# Motor_3.net
KiCad netlist of a schematic drawn in Altium Designer
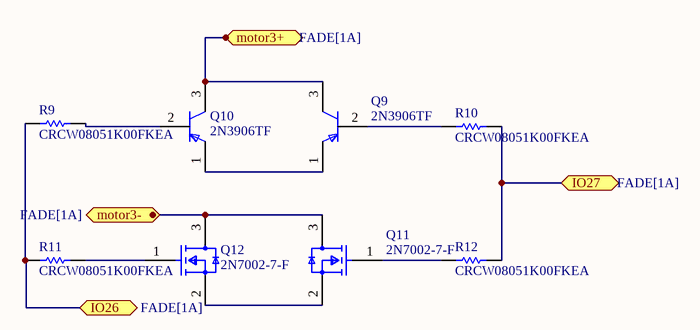
[diagram p0: Motor_3.SchDoc]

(export (version "E")
  (design (tool "Eeschema 10.0.6"))
  (components
    (comp (ref "Q9")
      (value "2N3906TF")
      (footprint "FP-135AR-MFG")
      (description "2N3906TF Small Signal Bipolar Transistor, 0.2A I(C), 40V V(BR)CEO, 1-Element, PNP, Silicon, TO-92")
      (libsource (lib "Altium Content Vault") (part "40d2b7e180a7bcff784209620afba3e"))
    )
    (comp (ref "Q10")
      (value "2N3906TF")
      (footprint "FP-135AR-MFG")
      (description "2N3906TF Small Signal Bipolar Transistor, 0.2A I(C), 40V V(BR)CEO, 1-Element, PNP, Silicon, TO-92")
      (libsource (lib "Altium Content Vault") (part "40d2b7e180a7bcff784209620afba3e"))
    )
    (comp (ref "Q11")
      (value "2N7002-7-F")
      (footprint "FP-SOT23-MFG")
      (description "MOSFET N-CH 60V 115MA SOT23-3")
      (fields (field (name "VOLTAGE") "60V"))
      (libsource (lib "Altium Content Vault") (part "3b9c635fedb024a5347a57b145af9cc"))
    )
    (comp (ref "Q12")
      (value "2N7002-7-F")
      (footprint "FP-SOT23-MFG")
      (description "MOSFET N-CH 60V 115MA SOT23-3")
      (fields (field (name "VOLTAGE") "60V"))
      (libsource (lib "Altium Content Vault") (part "3b9c635fedb024a5347a57b145af9cc"))
    )
    (comp (ref "R9")
      (value "CRCW08051K00FKEA")
      (footprint "RESC2013X50X30NL20T20")
      (fields (field (name "MANUFACTURER") "Vishay Dale"))
      (libsource (lib "Altium Content Vault") (part "RES"))
    )
    (comp (ref "R10")
      (value "CRCW08051K00FKEA")
      (footprint "RESC2013X50X30NL20T20")
      (fields (field (name "MANUFACTURER") "Vishay Dale"))
      (libsource (lib "Altium Content Vault") (part "RES"))
    )
    (comp (ref "R11")
      (value "CRCW08051K00FKEA")
      (footprint "RESC2013X50X30NL20T20")
      (fields (field (name "MANUFACTURER") "Vishay Dale"))
      (libsource (lib "Altium Content Vault") (part "RES"))
    )
    (comp (ref "R12")
      (value "CRCW08051K00FKEA")
      (footprint "RESC2013X50X30NL20T20")
      (fields (field (name "MANUFACTURER") "Vishay Dale"))
      (libsource (lib "Altium Content Vault") (part "RES"))
    )
  )
  (nets
    (net (code "1") (name "/IO26") (class "Default")
      (node (ref "R11") (pin "1") (pinfunction "1_1") (pintype "passive"))
      (node (ref "R9") (pin "1") (pinfunction "1_1") (pintype "passive"))
    )
    (net (code "2") (name "/IO27") (class "Default")
      (node (ref "R10") (pin "2") (pinfunction "2_2") (pintype "passive"))
      (node (ref "R12") (pin "2") (pinfunction "2_2") (pintype "passive"))
    )
    (net (code "3") (name "/motor3+") (class "Default")
      (node (ref "Q10") (pin "3") (pinfunction "C_3") (pintype "passive"))
      (node (ref "Q9") (pin "3") (pinfunction "C_3") (pintype "passive"))
    )
    (net (code "4") (name "/motor3-") (class "Default")
      (node (ref "Q11") (pin "3") (pinfunction "D_3") (pintype "passive"))
      (node (ref "Q12") (pin "3") (pinfunction "D_3") (pintype "passive"))
    )
    (net (code "5") (name "Net-(Q9-B)") (class "Default")
      (node (ref "Q9") (pin "2") (pinfunction "B_2") (pintype "passive"))
      (node (ref "R10") (pin "1") (pinfunction "1_1") (pintype "passive"))
    )
    (net (code "6") (name "Net-(Q10-B)") (class "Default")
      (node (ref "Q10") (pin "2") (pinfunction "B_2") (pintype "passive"))
      (node (ref "R9") (pin "2") (pinfunction "2_2") (pintype "passive"))
    )
    (net (code "7") (name "Net-(Q10-E)") (class "Default")
      (node (ref "Q10") (pin "1") (pinfunction "E_1") (pintype "passive"))
      (node (ref "Q9") (pin "1") (pinfunction "E_1") (pintype "passive"))
    )
    (net (code "8") (name "Net-(Q11-G)") (class "Default")
      (node (ref "Q11") (pin "1") (pinfunction "G_1") (pintype "passive"))
      (node (ref "R12") (pin "1") (pinfunction "1_1") (pintype "passive"))
    )
    (net (code "9") (name "Net-(Q11-S)") (class "Default")
      (node (ref "Q11") (pin "2") (pinfunction "S_2") (pintype "passive"))
      (node (ref "Q12") (pin "2") (pinfunction "S_2") (pintype "passive"))
    )
    (net (code "10") (name "Net-(Q12-G)") (class "Default")
      (node (ref "Q12") (pin "1") (pinfunction "G_1") (pintype "passive"))
      (node (ref "R11") (pin "2") (pinfunction "2_2") (pintype "passive"))
    )
  )
)
